# Transceiver.net
KiCad netlist of a schematic drawn in EAGLE
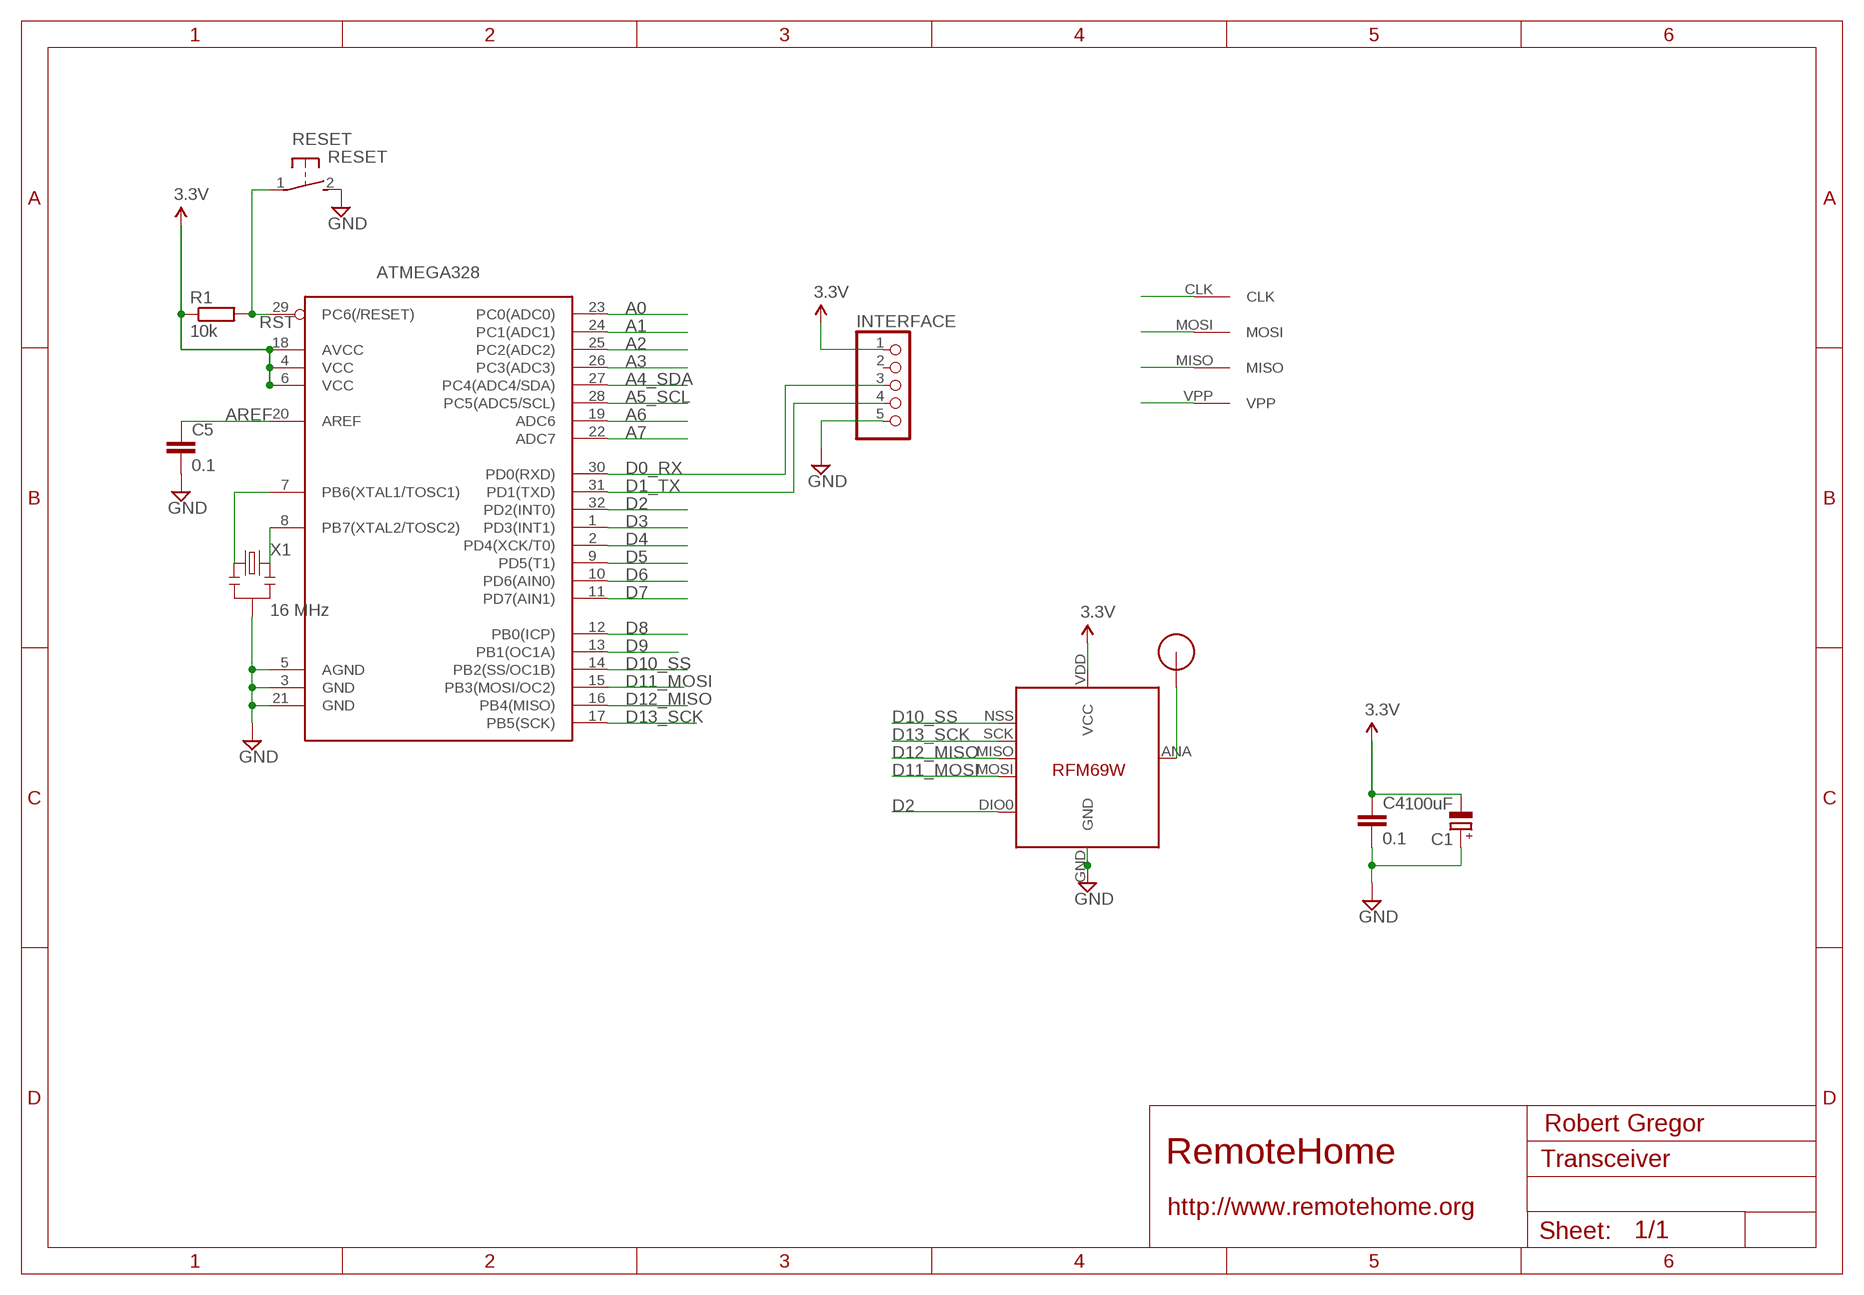
[diagram p0: schematic, sheet 1]

(export (version "E")
  (design (tool "Eeschema 10.0.6"))
  (components
    (comp (ref "ATMEGA328")
      (value "ATMega-328")
      (footprint "eagle-import:TQFP32-08")
      (libsource (lib "eagle-import") (part "ATMEGA168/328TQFP32"))
    )
    (comp (ref "C1")
      (value "100uF")
      (footprint "eagle-import:SMC_B")
      (libsource (lib "eagle-import") (part "CPOL-EUSMCB"))
    )
    (comp (ref "C4")
      (value "0.1")
      (footprint "eagle-import:C2012")
      (libsource (lib "eagle-import") (part "C-EUC2012"))
    )
    (comp (ref "C5")
      (value "0.1")
      (footprint "eagle-import:C2012")
      (libsource (lib "eagle-import") (part "C-EUC2012"))
    )
    (comp (ref "INTERFACE")
      (value "PINHD-1X05_2.54-S")
      (footprint "eagle-import:1X05-S")
      (libsource (lib "eagle-import") (part "PINHD-1X05_2.54-S"))
    )
    (comp (ref "R1")
      (value "10k")
      (footprint "eagle-import:R2012")
      (libsource (lib "eagle-import") (part "R-EU_R2012"))
    )
    (comp (ref "RESET")
      (value "RESET")
      (footprint "eagle-import:DTSM-3")
      (libsource (lib "eagle-import") (part "DTSM-3"))
    )
    (comp (ref "U$1")
      (value "RFM12B_ANTENNA")
      (footprint "eagle-import:RFM12B-ANTENNA")
      (libsource (lib "eagle-import") (part "RFM12B_ANTENNA"))
    )
    (comp (ref "U$2")
      (value "AVRHEADERDIP")
      (footprint "eagle-import:AVRHEADER")
      (libsource (lib "eagle-import") (part "AVRHEADERDIP"))
    )
    (comp (ref "U$5")
      (value "RFM69")
      (footprint "eagle-import:RFM69W-MINPADS")
      (libsource (lib "eagle-import") (part "RFM69"))
    )
    (comp (ref "X1")
      (value "16 MHz")
      (footprint "eagle-import:RESONATOR-SMD")
      (libsource (lib "eagle-import") (part "RESONATORSMD"))
    )
  )
  (nets
    (net (code "1") (name "/A0") (class "Default")
      (node (ref "ATMEGA328") (pin "23") (pinfunction "PC0(ADC0)_23") (pintype "bidirectional"))
    )
    (net (code "2") (name "/A1") (class "Default")
      (node (ref "ATMEGA328") (pin "24") (pinfunction "PC1(ADC1)_24") (pintype "bidirectional"))
    )
    (net (code "3") (name "/A2") (class "Default")
      (node (ref "ATMEGA328") (pin "25") (pinfunction "PC2(ADC2)_25") (pintype "bidirectional"))
    )
    (net (code "4") (name "/A3") (class "Default")
      (node (ref "ATMEGA328") (pin "26") (pinfunction "PC3(ADC3)_26") (pintype "bidirectional"))
    )
    (net (code "5") (name "/A4_SDA") (class "Default")
      (node (ref "ATMEGA328") (pin "27") (pinfunction "PC4(ADC4/SDA)_27") (pintype "bidirectional"))
    )
    (net (code "6") (name "/A5_SCL") (class "Default")
      (node (ref "ATMEGA328") (pin "28") (pinfunction "PC5(ADC5/SCL)_28") (pintype "bidirectional"))
    )
    (net (code "7") (name "/A6") (class "Default")
      (node (ref "ATMEGA328") (pin "19") (pinfunction "ADC6_19") (pintype "bidirectional"))
    )
    (net (code "8") (name "/A7") (class "Default")
      (node (ref "ATMEGA328") (pin "22") (pinfunction "ADC7_22") (pintype "bidirectional"))
    )
    (net (code "9") (name "/AREF") (class "Default")
      (node (ref "ATMEGA328") (pin "20") (pinfunction "AREF_20") (pintype "bidirectional"))
      (node (ref "C5") (pin "1") (pinfunction "1_1") (pintype "passive"))
    )
    (net (code "10") (name "/D0_RX") (class "Default")
      (node (ref "ATMEGA328") (pin "30") (pinfunction "PD0(RXD)_30") (pintype "bidirectional"))
      (node (ref "INTERFACE") (pin "3") (pinfunction "3_3") (pintype "passive"))
    )
    (net (code "11") (name "/D1_TX") (class "Default")
      (node (ref "ATMEGA328") (pin "31") (pinfunction "PD1(TXD)_31") (pintype "bidirectional"))
      (node (ref "INTERFACE") (pin "4") (pinfunction "4_4") (pintype "passive"))
    )
    (net (code "12") (name "/D2") (class "Default")
      (node (ref "ATMEGA328") (pin "32") (pinfunction "PD2(INT0)_32") (pintype "bidirectional"))
      (node (ref "U$5") (pin "DIO0") (pinfunction "DIO0_DIO0") (pintype "open_collector"))
    )
    (net (code "13") (name "/D3") (class "Default")
      (node (ref "ATMEGA328") (pin "1") (pinfunction "PD3(INT1)_1") (pintype "bidirectional"))
    )
    (net (code "14") (name "/D4") (class "Default")
      (node (ref "ATMEGA328") (pin "2") (pinfunction "PD4(XCK/T0)_2") (pintype "bidirectional"))
    )
    (net (code "15") (name "/D5") (class "Default")
      (node (ref "ATMEGA328") (pin "9") (pinfunction "PD5(T1)_9") (pintype "bidirectional"))
    )
    (net (code "16") (name "/D6") (class "Default")
      (node (ref "ATMEGA328") (pin "10") (pinfunction "PD6(AIN0)_10") (pintype "bidirectional"))
    )
    (net (code "17") (name "/D7") (class "Default")
      (node (ref "ATMEGA328") (pin "11") (pinfunction "PD7(AIN1)_11") (pintype "bidirectional"))
    )
    (net (code "18") (name "/D8") (class "Default")
      (node (ref "ATMEGA328") (pin "12") (pinfunction "PB0(ICP)_12") (pintype "bidirectional"))
    )
    (net (code "19") (name "/D9") (class "Default")
      (node (ref "ATMEGA328") (pin "13") (pinfunction "PB1(OC1A)_13") (pintype "bidirectional"))
    )
    (net (code "20") (name "/D10_SS") (class "Default")
      (node (ref "ATMEGA328") (pin "14") (pinfunction "PB2(SS/OC1B)_14") (pintype "bidirectional"))
      (node (ref "U$5") (pin "NSS") (pinfunction "SEL_NSS") (pintype "input"))
    )
    (net (code "21") (name "/D11_MOSI") (class "Default")
      (node (ref "ATMEGA328") (pin "15") (pinfunction "PB3(MOSI/OC2)_15") (pintype "bidirectional"))
      (node (ref "U$2") (pin "MOSI") (pinfunction "MOSI_MOSI") (pintype "bidirectional"))
      (node (ref "U$5") (pin "MOSI") (pinfunction "MOSI_MOSI") (pintype "output"))
    )
    (net (code "22") (name "/D12_MISO") (class "Default")
      (node (ref "ATMEGA328") (pin "16") (pinfunction "PB4(MISO)_16") (pintype "bidirectional"))
      (node (ref "U$2") (pin "MISO") (pinfunction "MISO_MISO") (pintype "bidirectional"))
      (node (ref "U$5") (pin "MISO") (pinfunction "MISO_MISO") (pintype "input"))
    )
    (net (code "23") (name "/D13_SCK") (class "Default")
      (node (ref "ATMEGA328") (pin "17") (pinfunction "PB5(SCK)_17") (pintype "bidirectional"))
      (node (ref "U$2") (pin "CLK") (pinfunction "CLK_CLK") (pintype "bidirectional"))
      (node (ref "U$5") (pin "SCK") (pinfunction "SCK_SCK") (pintype "input"))
    )
    (net (code "24") (name "/RST") (class "Default")
      (node (ref "ATMEGA328") (pin "29") (pinfunction "PC6(/RESET)_29") (pintype "bidirectional"))
      (node (ref "R1") (pin "2") (pinfunction "2_2") (pintype "passive"))
      (node (ref "RESET") (pin "1") (pinfunction "1_1") (pintype "passive"))
      (node (ref "U$2") (pin "VPP") (pinfunction "VPP_VPP") (pintype "bidirectional"))
    )
    (net (code "25") (name "3.3V") (class "Default")
      (node (ref "ATMEGA328") (pin "18") (pinfunction "AVCC_18") (pintype "bidirectional"))
      (node (ref "ATMEGA328") (pin "4") (pinfunction "VCC_4") (pintype "bidirectional"))
      (node (ref "ATMEGA328") (pin "6") (pinfunction "VCC_6") (pintype "bidirectional"))
      (node (ref "C1") (pin "-") (pinfunction "-_-") (pintype "passive"))
      (node (ref "C4") (pin "1") (pinfunction "1_1") (pintype "passive"))
      (node (ref "INTERFACE") (pin "1") (pinfunction "1_1") (pintype "passive"))
      (node (ref "R1") (pin "1") (pinfunction "1_1") (pintype "passive"))
      (node (ref "U$5") (pin "VDD") (pinfunction "VCC_VDD") (pintype "power_in"))
    )
    (net (code "26") (name "GND") (class "Default")
      (node (ref "ATMEGA328") (pin "21") (pinfunction "GND_21") (pintype "bidirectional"))
      (node (ref "ATMEGA328") (pin "3") (pinfunction "GND_3") (pintype "bidirectional"))
      (node (ref "ATMEGA328") (pin "5") (pinfunction "AGND_5") (pintype "bidirectional"))
      (node (ref "C1") (pin "+") (pinfunction "+_+") (pintype "passive"))
      (node (ref "C4") (pin "2") (pinfunction "2_2") (pintype "passive"))
      (node (ref "C5") (pin "2") (pinfunction "2_2") (pintype "passive"))
      (node (ref "INTERFACE") (pin "5") (pinfunction "5_5") (pintype "passive"))
      (node (ref "RESET") (pin "2") (pinfunction "2_2") (pintype "passive"))
      (node (ref "U$5") (pin "GND") (pinfunction "GND_GND") (pintype "power_in"))
      (node (ref "X1") (pin "2") (pinfunction "2_2") (pintype "passive"))
    )
    (net (code "27") (name "Net-(ATMEGA328-PB6(XTAL1{slash}TOSC1))") (class "Default")
      (node (ref "ATMEGA328") (pin "7") (pinfunction "PB6(XTAL1/TOSC1)_7") (pintype "bidirectional"))
      (node (ref "X1") (pin "1") (pinfunction "1_1") (pintype "passive"))
    )
    (net (code "28") (name "Net-(ATMEGA328-PB7(XTAL2{slash}TOSC2))") (class "Default")
      (node (ref "ATMEGA328") (pin "8") (pinfunction "PB7(XTAL2/TOSC2)_8") (pintype "bidirectional"))
      (node (ref "X1") (pin "3") (pinfunction "3_3") (pintype "passive"))
    )
    (net (code "29") (name "Net-(U$1-1)") (class "Default")
      (node (ref "U$1") (pin "P$1") (pinfunction "1_P$1") (pintype "bidirectional"))
      (node (ref "U$5") (pin "ANA") (pinfunction "ANT_ANA") (pintype "passive"))
    )
    (net (code "30") (name "unconnected-(INTERFACE-Pad2)") (class "Default")
      (node (ref "INTERFACE") (pin "2") (pinfunction "2_2") (pintype "passive"))
    )
  )
)
